# ATM90E26_Featherwing.net
KiCad netlist of a schematic drawn in EAGLE
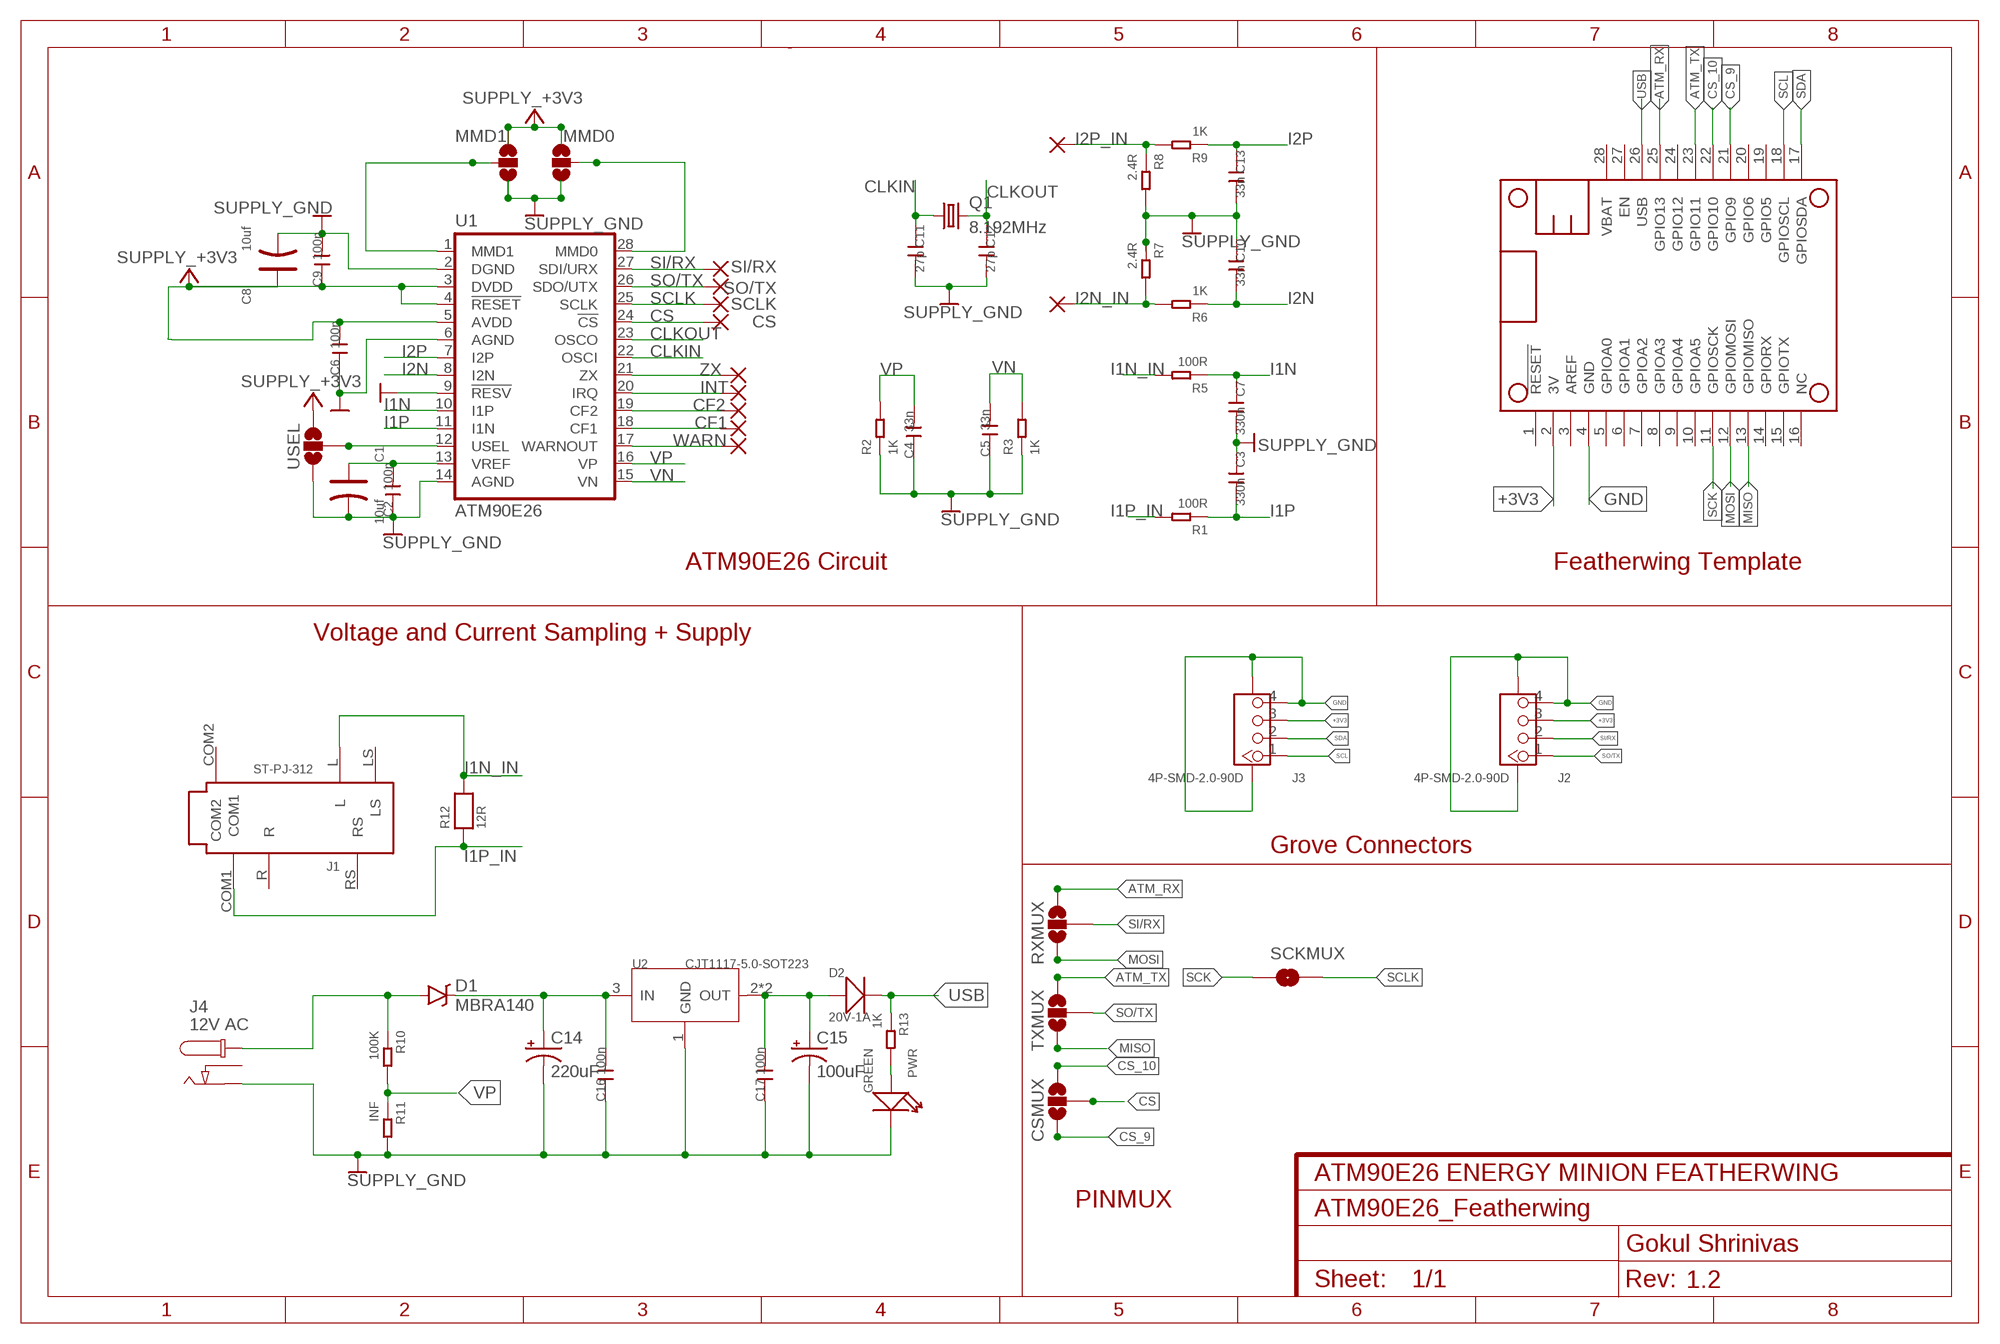
[diagram p0: schematic, sheet 1]

(export (version "E")
  (design (tool "Eeschema 10.0.6"))
  (components
    (comp (ref "C1")
      (value "10uf")
      (footprint "eagle-import:AVX-A")
      (fields (field (name "MPN") "TAJA226*010#NJ"))
      (libsource (lib "eagle-import") (part "TANTALUM-SMD-22UF-10V(AVX-A)"))
    )
    (comp (ref "C2")
      (value "100n")
      (footprint "eagle-import:C0603")
      (libsource (lib "eagle-import") (part "C-0603"))
    )
    (comp (ref "C3")
      (value "330n")
      (footprint "eagle-import:C0603")
      (libsource (lib "eagle-import") (part "C-0603"))
    )
    (comp (ref "C4")
      (value "33n")
      (footprint "eagle-import:C0603")
      (libsource (lib "eagle-import") (part "C-0603"))
    )
    (comp (ref "C5")
      (value "33n")
      (footprint "eagle-import:C0603")
      (libsource (lib "eagle-import") (part "C-0603"))
    )
    (comp (ref "C6")
      (value "100n")
      (footprint "eagle-import:C0603")
      (libsource (lib "eagle-import") (part "C-0603"))
    )
    (comp (ref "C7")
      (value "330n")
      (footprint "eagle-import:C0603")
      (libsource (lib "eagle-import") (part "C-0603"))
    )
    (comp (ref "C8")
      (value "10uf")
      (footprint "eagle-import:AVX-A")
      (fields (field (name "MPN") "TAJA226*010#NJ"))
      (libsource (lib "eagle-import") (part "TANTALUM-SMD-22UF-10V(AVX-A)"))
    )
    (comp (ref "C9")
      (value "100n")
      (footprint "eagle-import:C0603")
      (libsource (lib "eagle-import") (part "C-0603"))
    )
    (comp (ref "C10")
      (value "33n")
      (footprint "eagle-import:C0603")
      (libsource (lib "eagle-import") (part "C-0603"))
    )
    (comp (ref "C11")
      (value "27p")
      (footprint "eagle-import:C0603")
      (libsource (lib "eagle-import") (part "C-0603"))
    )
    (comp (ref "C12")
      (value "27p")
      (footprint "eagle-import:C0603")
      (libsource (lib "eagle-import") (part "C-0603"))
    )
    (comp (ref "C13")
      (value "33n")
      (footprint "eagle-import:C0603")
      (libsource (lib "eagle-import") (part "C-0603"))
    )
    (comp (ref "C14")
      (value "220uF")
      (footprint "eagle-import:140CLH-1010")
      (libsource (lib "eagle-import") (part "CPOL-US140CLH-1010"))
    )
    (comp (ref "C15")
      (value "100uF")
      (footprint "eagle-import:153CLV-0605")
      (libsource (lib "eagle-import") (part "CPOL-US153CLV-0605"))
    )
    (comp (ref "C16")
      (value "100n")
      (footprint "eagle-import:C0603")
      (libsource (lib "eagle-import") (part "C-0603"))
    )
    (comp (ref "C17")
      (value "100n")
      (footprint "eagle-import:C0603")
      (libsource (lib "eagle-import") (part "C-0603"))
    )
    (comp (ref "CF1")
      (value "WIREPADSMD1,27-254")
      (footprint "eagle-import:SMD1,27-2,54")
      (libsource (lib "eagle-import") (part "WIREPADSMD1,27-254"))
    )
    (comp (ref "CF2")
      (value "WIREPADSMD1,27-254")
      (footprint "eagle-import:SMD1,27-2,54")
      (libsource (lib "eagle-import") (part "WIREPADSMD1,27-254"))
    )
    (comp (ref "CS")
      (value "WIREPADSMD1,27-254")
      (footprint "eagle-import:SMD1,27-2,54")
      (libsource (lib "eagle-import") (part "WIREPADSMD1,27-254"))
    )
    (comp (ref "CSMUX")
      (value "JUMPER-PAD-3-NOYES_SILK")
      (footprint "eagle-import:PAD-JUMPER-3-NO_YES_SILK")
      (libsource (lib "eagle-import") (part "JUMPER-PAD-3-NOYES_SILK"))
    )
    (comp (ref "D1")
      (value "MBRA140")
      (footprint "eagle-import:SMA-DIODE")
      (libsource (lib "eagle-import") (part "MBRA140"))
    )
    (comp (ref "D2")
      (value "20V-1A")
      (footprint "eagle-import:SOD-123")
      (fields (field (name "MPN") "B5819W"))
      (libsource (lib "eagle-import") (part "SMD-DIODE-SCHOTTKY-20V-1A(SOD-123)"))
    )
    (comp (ref "I2N_IN")
      (value "WIREPADSMD1,27-254")
      (footprint "eagle-import:SMD1,27-2,54")
      (libsource (lib "eagle-import") (part "WIREPADSMD1,27-254"))
    )
    (comp (ref "I2P_IN")
      (value "WIREPADSMD1,27-254")
      (footprint "eagle-import:SMD1,27-2,54")
      (libsource (lib "eagle-import") (part "WIREPADSMD1,27-254"))
    )
    (comp (ref "INT")
      (value "WIREPADSMD1,27-254")
      (footprint "eagle-import:SMD1,27-2,54")
      (libsource (lib "eagle-import") (part "WIREPADSMD1,27-254"))
    )
    (comp (ref "J1")
      (value "ST-PJ-312")
      (footprint "eagle-import:AUDIO6P-SMD-3.5-14.0X6.4X5.0MM")
      (libsource (lib "eagle-import") (part "AUDIO-JACK-6P-SMD(ST-PJ-312)"))
    )
    (comp (ref "J2")
      (value "4P-SMD-2.0-90D")
      (footprint "eagle-import:HW4-SMD-2.0-90D")
      (libsource (lib "eagle-import") (part "GROVE-CONNECTOR-SMD-90D(4+2P-2.0)"))
    )
    (comp (ref "J3")
      (value "4P-SMD-2.0-90D")
      (footprint "eagle-import:HW4-SMD-2.0-90D")
      (libsource (lib "eagle-import") (part "GROVE-CONNECTOR-SMD-90D(4+2P-2.0)"))
    )
    (comp (ref "J4")
      (value "12V AC")
      (footprint "eagle-import:DC_BARREL_JACK_SMD_2MM")
      (libsource (lib "eagle-import") (part "CON_DC_M-DC_SMD"))
    )
    (comp (ref "MMD0")
      (value "JUMPER-PAD-3-NOFULL_BOX_SILK")
      (footprint "eagle-import:PAD-JUMPER-3-NO_YES_SILK_FULL_BOX")
      (libsource (lib "eagle-import") (part "JUMPER-PAD-3-NOFULL_BOX_SILK"))
    )
    (comp (ref "MMD1")
      (value "JUMPER-PAD-3-NOFULL_BOX_SILK")
      (footprint "eagle-import:PAD-JUMPER-3-NO_YES_SILK_FULL_BOX")
      (libsource (lib "eagle-import") (part "JUMPER-PAD-3-NOFULL_BOX_SILK"))
    )
    (comp (ref "MS1")
      (value "FEATHERWING_NODIM")
      (footprint "eagle-import:FEATHERWING_DIM")
      (libsource (lib "eagle-import") (part "FEATHERWING_NODIM"))
    )
    (comp (ref "PWR")
      (value "GREEN")
      (footprint "eagle-import:LED-0603")
      (libsource (lib "eagle-import") (part "LED'0603'"))
    )
    (comp (ref "Q1")
      (value "8.192MHz")
      (footprint "eagle-import:HC49UP")
      (libsource (lib "eagle-import") (part "CRYSTALHC49UP"))
    )
    (comp (ref "R1")
      (value "100R")
      (footprint "eagle-import:R0603")
      (fields (field (name "MPN") "RC0603FR-071KL"))
      (libsource (lib "eagle-import") (part "SMD-RES-1K(0603)"))
    )
    (comp (ref "R2")
      (value "1K")
      (footprint "eagle-import:R0603")
      (fields (field (name "MPN") "RC0603FR-071KL"))
      (libsource (lib "eagle-import") (part "SMD-RES-1K(0603)"))
    )
    (comp (ref "R3")
      (value "1K")
      (footprint "eagle-import:R0603")
      (fields (field (name "MPN") "RC0603FR-071KL"))
      (libsource (lib "eagle-import") (part "SMD-RES-1K(0603)"))
    )
    (comp (ref "R5")
      (value "100R")
      (footprint "eagle-import:R0603")
      (fields (field (name "MPN") "RC0603FR-071KL"))
      (libsource (lib "eagle-import") (part "SMD-RES-1K(0603)"))
    )
    (comp (ref "R6")
      (value "1K")
      (footprint "eagle-import:R0603")
      (fields (field (name "MPN") "RC0603FR-071KL"))
      (libsource (lib "eagle-import") (part "SMD-RES-1K(0603)"))
    )
    (comp (ref "R7")
      (value "2.4R")
      (footprint "eagle-import:R0603")
      (fields (field (name "MPN") "RC0603FR-071KL"))
      (libsource (lib "eagle-import") (part "SMD-RES-1K(0603)"))
    )
    (comp (ref "R8")
      (value "2.4R")
      (footprint "eagle-import:R0603")
      (fields (field (name "MPN") "RC0603FR-071KL"))
      (libsource (lib "eagle-import") (part "SMD-RES-1K(0603)"))
    )
    (comp (ref "R9")
      (value "1K")
      (footprint "eagle-import:R0603")
      (fields (field (name "MPN") "RC0603FR-071KL"))
      (libsource (lib "eagle-import") (part "SMD-RES-1K(0603)"))
    )
    (comp (ref "R10")
      (value "100K")
      (footprint "eagle-import:R0603")
      (fields (field (name "MPN") "RC0603JR-070RL"))
      (libsource (lib "eagle-import") (part "SMD-RES-0R(0603)"))
    )
    (comp (ref "R11")
      (value "INF")
      (footprint "eagle-import:R0603")
      (fields (field (name "MPN") "RC0603JR-070RL"))
      (libsource (lib "eagle-import") (part "SMD-RES-0R(0603)"))
    )
    (comp (ref "R12")
      (value "12R")
      (footprint "eagle-import:0805")
      (libsource (lib "eagle-import") (part "RESISTOR0805"))
    )
    (comp (ref "R13")
      (value "1K")
      (footprint "eagle-import:R0603")
      (fields (field (name "MPN") "RC0603JR-070RL"))
      (libsource (lib "eagle-import") (part "SMD-RES-0R(0603)"))
    )
    (comp (ref "RXMUX")
      (value "JUMPER-PAD-3-NOYES_SILK")
      (footprint "eagle-import:PAD-JUMPER-3-NO_YES_SILK")
      (libsource (lib "eagle-import") (part "JUMPER-PAD-3-NOYES_SILK"))
    )
    (comp (ref "SCKMUX")
      (value "JUMPER-PAD-2-NOYES_SILK")
      (footprint "eagle-import:PAD-JUMPER-2-NO_YES_SILK")
      (libsource (lib "eagle-import") (part "JUMPER-PAD-2-NOYES_SILK"))
    )
    (comp (ref "SCLK")
      (value "WIREPADSMD1,27-254")
      (footprint "eagle-import:SMD1,27-2,54")
      (libsource (lib "eagle-import") (part "WIREPADSMD1,27-254"))
    )
    (comp (ref "SI/RX")
      (value "WIREPADSMD1,27-254")
      (footprint "eagle-import:SMD1,27-2,54")
      (libsource (lib "eagle-import") (part "WIREPADSMD1,27-254"))
    )
    (comp (ref "SO/TX")
      (value "WIREPADSMD1,27-254")
      (footprint "eagle-import:SMD1,27-2,54")
      (libsource (lib "eagle-import") (part "WIREPADSMD1,27-254"))
    )
    (comp (ref "TXMUX")
      (value "JUMPER-PAD-3-NOYES_SILK")
      (footprint "eagle-import:PAD-JUMPER-3-NO_YES_SILK")
      (libsource (lib "eagle-import") (part "JUMPER-PAD-3-NOYES_SILK"))
    )
    (comp (ref "U1")
      (value "ATM90E26")
      (footprint "eagle-import:SSOP-28")
      (fields (field (name "MANF") "Atmel"))
      (libsource (lib "eagle-import") (part "ATM90E26"))
    )
    (comp (ref "U2")
      (value "CJT1117-5.0-SOT223")
      (footprint "eagle-import:SOT-223")
      (fields (field (name "MPN") "CJT1117-5.0"))
      (libsource (lib "eagle-import") (part "PMIC-CJT1117-5.0(SOT223)"))
    )
    (comp (ref "USEL")
      (value "JUMPER-PAD-3-NOFULL_BOX_SILK")
      (footprint "eagle-import:PAD-JUMPER-3-NO_YES_SILK_FULL_BOX")
      (libsource (lib "eagle-import") (part "JUMPER-PAD-3-NOFULL_BOX_SILK"))
    )
    (comp (ref "WARN")
      (value "WIREPADSMD1,27-254")
      (footprint "eagle-import:SMD1,27-2,54")
      (libsource (lib "eagle-import") (part "WIREPADSMD1,27-254"))
    )
    (comp (ref "ZX")
      (value "WIREPADSMD1,27-254")
      (footprint "eagle-import:SMD1,27-2,54")
      (libsource (lib "eagle-import") (part "WIREPADSMD1,27-254"))
    )
  )
  (nets
    (net (code "1") (name "+3V3") (class "Default")
      (node (ref "C6") (pin "2") (pinfunction "2_2") (pintype "passive"))
      (node (ref "C8") (pin "+") (pinfunction "+_+") (pintype "passive"))
      (node (ref "C9") (pin "1") (pinfunction "1_1") (pintype "passive"))
      (node (ref "J2") (pin "3") (pinfunction "3_3") (pintype "bidirectional"))
      (node (ref "J3") (pin "3") (pinfunction "3_3") (pintype "bidirectional"))
      (node (ref "MMD0") (pin "3") (pinfunction "3_3") (pintype "passive"))
      (node (ref "MMD1") (pin "1") (pinfunction "1_1") (pintype "passive"))
      (node (ref "MS1") (pin "2") (pinfunction "3V_2") (pintype "power_in"))
      (node (ref "U1") (pin "3") (pinfunction "DVDD_3") (pintype "power_in"))
      (node (ref "U1") (pin "4") (pinfunction "~{RESET}_4") (pintype "input"))
      (node (ref "U1") (pin "5") (pinfunction "AVDD_5") (pintype "power_in"))
      (node (ref "USEL") (pin "3") (pinfunction "3_3") (pintype "passive"))
    )
    (net (code "2") (name "/CLKIN") (class "Default")
      (node (ref "C11") (pin "1") (pinfunction "1_1") (pintype "passive"))
      (node (ref "Q1") (pin "1") (pinfunction "1_1") (pintype "passive"))
      (node (ref "U1") (pin "22") (pinfunction "OSCI_22") (pintype "input"))
    )
    (net (code "3") (name "/CLKOUT") (class "Default")
      (node (ref "C12") (pin "1") (pinfunction "1_1") (pintype "passive"))
      (node (ref "Q1") (pin "2") (pinfunction "2_2") (pintype "passive"))
      (node (ref "U1") (pin "23") (pinfunction "OSCO_23") (pintype "output"))
    )
    (net (code "4") (name "/I1N") (class "Default")
      (node (ref "C7") (pin "1") (pinfunction "1_1") (pintype "passive"))
      (node (ref "R5") (pin "1") (pinfunction "1_1") (pintype "passive"))
      (node (ref "U1") (pin "10") (pinfunction "I1P_10") (pintype "input"))
    )
    (net (code "5") (name "/I1N_IN") (class "Default")
      (node (ref "J1") (pin "L") (pinfunction "L_L") (pintype "bidirectional"))
      (node (ref "R12") (pin "2") (pinfunction "2_2") (pintype "passive"))
      (node (ref "R5") (pin "2") (pinfunction "2_2") (pintype "passive"))
    )
    (net (code "6") (name "/I1P") (class "Default")
      (node (ref "C3") (pin "2") (pinfunction "2_2") (pintype "passive"))
      (node (ref "R1") (pin "1") (pinfunction "1_1") (pintype "passive"))
      (node (ref "U1") (pin "11") (pinfunction "I1N_11") (pintype "input"))
    )
    (net (code "7") (name "/I1P_IN") (class "Default")
      (node (ref "J1") (pin "COM1") (pinfunction "COM1_COM1") (pintype "bidirectional"))
      (node (ref "R1") (pin "2") (pinfunction "2_2") (pintype "passive"))
      (node (ref "R12") (pin "1") (pinfunction "1_1") (pintype "passive"))
    )
    (net (code "8") (name "/I2N") (class "Default")
      (node (ref "C10") (pin "2") (pinfunction "2_2") (pintype "passive"))
      (node (ref "R6") (pin "1") (pinfunction "1_1") (pintype "passive"))
      (node (ref "U1") (pin "8") (pinfunction "I2N_8") (pintype "input"))
    )
    (net (code "9") (name "/I2N_IN") (class "Default")
      (node (ref "I2N_IN") (pin "1") (pinfunction "P_1") (pintype "passive"))
      (node (ref "R6") (pin "2") (pinfunction "2_2") (pintype "passive"))
      (node (ref "R7") (pin "2") (pinfunction "2_2") (pintype "passive"))
    )
    (net (code "10") (name "/I2P") (class "Default")
      (node (ref "C13") (pin "1") (pinfunction "1_1") (pintype "passive"))
      (node (ref "R9") (pin "1") (pinfunction "1_1") (pintype "passive"))
      (node (ref "U1") (pin "7") (pinfunction "I2P_7") (pintype "input"))
    )
    (net (code "11") (name "/I2P_IN") (class "Default")
      (node (ref "I2P_IN") (pin "1") (pinfunction "P_1") (pintype "passive"))
      (node (ref "R8") (pin "1") (pinfunction "1_1") (pintype "passive"))
      (node (ref "R9") (pin "2") (pinfunction "2_2") (pintype "passive"))
    )
    (net (code "12") (name "/VBAT") (class "Default")
      (node (ref "MS1") (pin "28") (pinfunction "VBAT_28") (pintype "power_in"))
    )
    (net (code "13") (name "/VN") (class "Default")
      (node (ref "C5") (pin "2") (pinfunction "2_2") (pintype "passive"))
      (node (ref "R3") (pin "2") (pinfunction "2_2") (pintype "passive"))
      (node (ref "U1") (pin "15") (pinfunction "VN_15") (pintype "input"))
    )
    (net (code "14") (name "ATM_RX") (class "Default")
      (node (ref "MS1") (pin "25") (pinfunction "GPIO13_25") (pintype "bidirectional"))
      (node (ref "RXMUX") (pin "3") (pinfunction "3_3") (pintype "passive"))
    )
    (net (code "15") (name "ATM_TX") (class "Default")
      (node (ref "MS1") (pin "23") (pinfunction "GPIO11_23") (pintype "bidirectional"))
      (node (ref "TXMUX") (pin "3") (pinfunction "3_3") (pintype "passive"))
    )
    (net (code "16") (name "CS") (class "Default")
      (node (ref "CS") (pin "1") (pinfunction "P_1") (pintype "passive"))
      (node (ref "CSMUX") (pin "2") (pinfunction "2_2") (pintype "passive"))
      (node (ref "U1") (pin "24") (pinfunction "~{CS}_24") (pintype "input"))
    )
    (net (code "17") (name "CS_9") (class "Default")
      (node (ref "CSMUX") (pin "1") (pinfunction "1_1") (pintype "passive"))
      (node (ref "MS1") (pin "21") (pinfunction "GPIO9_21") (pintype "bidirectional"))
    )
    (net (code "18") (name "CS_10") (class "Default")
      (node (ref "CSMUX") (pin "3") (pinfunction "3_3") (pintype "passive"))
      (node (ref "MS1") (pin "22") (pinfunction "GPIO10_22") (pintype "bidirectional"))
    )
    (net (code "19") (name "GND") (class "Default")
      (node (ref "C1") (pin "-") (pinfunction "-_-") (pintype "passive"))
      (node (ref "C10") (pin "1") (pinfunction "1_1") (pintype "passive"))
      (node (ref "C11") (pin "2") (pinfunction "2_2") (pintype "passive"))
      (node (ref "C12") (pin "2") (pinfunction "2_2") (pintype "passive"))
      (node (ref "C13") (pin "2") (pinfunction "2_2") (pintype "passive"))
      (node (ref "C14") (pin "-") (pinfunction "-_-") (pintype "passive"))
      (node (ref "C15") (pin "-") (pinfunction "-_-") (pintype "passive"))
      (node (ref "C16") (pin "1") (pinfunction "1_1") (pintype "passive"))
      (node (ref "C17") (pin "1") (pinfunction "1_1") (pintype "passive"))
      (node (ref "C2") (pin "1") (pinfunction "1_1") (pintype "passive"))
      (node (ref "C3") (pin "1") (pinfunction "1_1") (pintype "passive"))
      (node (ref "C4") (pin "1") (pinfunction "1_1") (pintype "passive"))
      (node (ref "C5") (pin "1") (pinfunction "1_1") (pintype "passive"))
      (node (ref "C6") (pin "1") (pinfunction "1_1") (pintype "passive"))
      (node (ref "C7") (pin "2") (pinfunction "2_2") (pintype "passive"))
      (node (ref "C8") (pin "-") (pinfunction "-_-") (pintype "passive"))
      (node (ref "C9") (pin "2") (pinfunction "2_2") (pintype "passive"))
      (node (ref "J2") (pin "4") (pinfunction "4_4") (pintype "bidirectional"))
      (node (ref "J2") (pin "SS1") (pinfunction "SS1_SS1") (pintype "bidirectional"))
      (node (ref "J2") (pin "SS2") (pinfunction "SS2_SS2") (pintype "bidirectional"))
      (node (ref "J3") (pin "4") (pinfunction "4_4") (pintype "bidirectional"))
      (node (ref "J3") (pin "SS1") (pinfunction "SS1_SS1") (pintype "bidirectional"))
      (node (ref "J3") (pin "SS2") (pinfunction "SS2_SS2") (pintype "bidirectional"))
      (node (ref "J4") (pin "P2") (pinfunction "P2_P2") (pintype "passive"))
      (node (ref "MMD0") (pin "1") (pinfunction "1_1") (pintype "passive"))
      (node (ref "MMD1") (pin "3") (pinfunction "3_3") (pintype "passive"))
      (node (ref "MS1") (pin "4") (pinfunction "GND_4") (pintype "power_in"))
      (node (ref "PWR") (pin "-") (pinfunction "-_-") (pintype "passive"))
      (node (ref "R11") (pin "2") (pinfunction "2_2") (pintype "passive"))
      (node (ref "R2") (pin "1") (pinfunction "1_1") (pintype "passive"))
      (node (ref "R3") (pin "1") (pinfunction "1_1") (pintype "passive"))
      (node (ref "R7") (pin "1") (pinfunction "1_1") (pintype "passive"))
      (node (ref "R8") (pin "2") (pinfunction "2_2") (pintype "passive"))
      (node (ref "U1") (pin "14") (pinfunction "AGND_14") (pintype "power_in"))
      (node (ref "U1") (pin "2") (pinfunction "DGND_2") (pintype "power_in"))
      (node (ref "U1") (pin "6") (pinfunction "AGND_6") (pintype "power_in"))
      (node (ref "U1") (pin "9") (pinfunction "~{RESV}_9") (pintype "input"))
      (node (ref "U2") (pin "1") (pinfunction "GND_1") (pintype "bidirectional"))
      (node (ref "USEL") (pin "1") (pinfunction "1_1") (pintype "passive"))
    )
    (net (code "20") (name "MISO") (class "Default")
      (node (ref "MS1") (pin "13") (pinfunction "GPIOMISO_13") (pintype "bidirectional"))
      (node (ref "TXMUX") (pin "1") (pinfunction "1_1") (pintype "passive"))
    )
    (net (code "21") (name "MOSI") (class "Default")
      (node (ref "MS1") (pin "12") (pinfunction "GPIOMOSI_12") (pintype "bidirectional"))
      (node (ref "RXMUX") (pin "1") (pinfunction "1_1") (pintype "passive"))
    )
    (net (code "22") (name "Net-(C15-Pad+)") (class "Default")
      (node (ref "C15") (pin "+") (pinfunction "+_+") (pintype "passive"))
      (node (ref "C17") (pin "2") (pinfunction "2_2") (pintype "passive"))
      (node (ref "D2") (pin "+") (pinfunction "+_+") (pintype "passive"))
      (node (ref "U2") (pin "2") (pinfunction "OUT_2") (pintype "bidirectional"))
      (node (ref "U2") (pin "TER") (pinfunction "OUT_TER") (pintype "bidirectional"))
    )
    (net (code "23") (name "Net-(CF1-P)") (class "Default")
      (node (ref "CF1") (pin "1") (pinfunction "P_1") (pintype "passive"))
      (node (ref "U1") (pin "18") (pinfunction "CF1_18") (pintype "output"))
    )
    (net (code "24") (name "Net-(CF2-P)") (class "Default")
      (node (ref "CF2") (pin "1") (pinfunction "P_1") (pintype "passive"))
      (node (ref "U1") (pin "19") (pinfunction "CF2_19") (pintype "output"))
    )
    (net (code "25") (name "Net-(INT-P)") (class "Default")
      (node (ref "INT") (pin "1") (pinfunction "P_1") (pintype "passive"))
      (node (ref "U1") (pin "20") (pinfunction "IRQ_20") (pintype "output"))
    )
    (net (code "26") (name "Net-(J4-P1)") (class "Default")
      (node (ref "D1") (pin "A") (pinfunction "A_A") (pintype "passive"))
      (node (ref "J4") (pin "P1@2") (pinfunction "P1_P1@2") (pintype "passive"))
      (node (ref "R10") (pin "1") (pinfunction "1_1") (pintype "passive"))
    )
    (net (code "27") (name "Net-(PWR-Pad+)") (class "Default")
      (node (ref "PWR") (pin "+") (pinfunction "+_+") (pintype "passive"))
      (node (ref "R13") (pin "2") (pinfunction "2_2") (pintype "passive"))
    )
    (net (code "28") (name "Net-(U1-MMD0)") (class "Default")
      (node (ref "MMD0") (pin "2") (pinfunction "2_2") (pintype "passive"))
      (node (ref "U1") (pin "28") (pinfunction "MMD0_28") (pintype "input"))
    )
    (net (code "29") (name "Net-(U1-MMD1)") (class "Default")
      (node (ref "MMD1") (pin "2") (pinfunction "2_2") (pintype "passive"))
      (node (ref "U1") (pin "1") (pinfunction "MMD1_1") (pintype "input"))
    )
    (net (code "30") (name "Net-(U1-USEL)") (class "Default")
      (node (ref "U1") (pin "12") (pinfunction "USEL_12") (pintype "input"))
      (node (ref "USEL") (pin "2") (pinfunction "2_2") (pintype "passive"))
    )
    (net (code "31") (name "Net-(U1-VREF)") (class "Default")
      (node (ref "C1") (pin "+") (pinfunction "+_+") (pintype "passive"))
      (node (ref "C2") (pin "2") (pinfunction "2_2") (pintype "passive"))
      (node (ref "U1") (pin "13") (pinfunction "VREF_13") (pintype "power_in"))
    )
    (net (code "32") (name "Net-(U1-WARNOUT)") (class "Default")
      (node (ref "U1") (pin "17") (pinfunction "WARNOUT_17") (pintype "output"))
      (node (ref "WARN") (pin "1") (pinfunction "P_1") (pintype "passive"))
    )
    (net (code "33") (name "Net-(U1-ZX)") (class "Default")
      (node (ref "U1") (pin "21") (pinfunction "ZX_21") (pintype "bidirectional"))
      (node (ref "ZX") (pin "1") (pinfunction "P_1") (pintype "passive"))
    )
    (net (code "34") (name "Net-(U2-IN)") (class "Default")
      (node (ref "C14") (pin "+") (pinfunction "+_+") (pintype "passive"))
      (node (ref "C16") (pin "2") (pinfunction "2_2") (pintype "passive"))
      (node (ref "D1") (pin "C") (pinfunction "C_C") (pintype "passive"))
      (node (ref "U2") (pin "3") (pinfunction "IN_3") (pintype "bidirectional"))
    )
    (net (code "35") (name "SCK") (class "Default")
      (node (ref "MS1") (pin "11") (pinfunction "GPIOSCK_11") (pintype "bidirectional"))
      (node (ref "SCKMUX") (pin "1") (pinfunction "1_1") (pintype "passive"))
    )
    (net (code "36") (name "SCL") (class "Default")
      (node (ref "J3") (pin "1") (pinfunction "1_1") (pintype "bidirectional"))
      (node (ref "MS1") (pin "18") (pinfunction "GPIOSCL_18") (pintype "bidirectional"))
    )
    (net (code "37") (name "SCLK") (class "Default")
      (node (ref "SCKMUX") (pin "2") (pinfunction "2_2") (pintype "passive"))
      (node (ref "SCLK") (pin "1") (pinfunction "P_1") (pintype "passive"))
      (node (ref "U1") (pin "25") (pinfunction "SCLK_25") (pintype "input"))
    )
    (net (code "38") (name "SDA") (class "Default")
      (node (ref "J3") (pin "2") (pinfunction "2_2") (pintype "bidirectional"))
      (node (ref "MS1") (pin "17") (pinfunction "GPIOSDA_17") (pintype "bidirectional"))
    )
    (net (code "39") (name "SI{slash}RX") (class "Default")
      (node (ref "J2") (pin "2") (pinfunction "2_2") (pintype "bidirectional"))
      (node (ref "RXMUX") (pin "2") (pinfunction "2_2") (pintype "passive"))
      (node (ref "SI/RX") (pin "1") (pinfunction "P_1") (pintype "passive"))
      (node (ref "U1") (pin "27") (pinfunction "SDI/URX_27") (pintype "input"))
    )
    (net (code "40") (name "SO{slash}TX") (class "Default")
      (node (ref "J2") (pin "1") (pinfunction "1_1") (pintype "bidirectional"))
      (node (ref "SO/TX") (pin "1") (pinfunction "P_1") (pintype "passive"))
      (node (ref "TXMUX") (pin "2") (pinfunction "2_2") (pintype "passive"))
      (node (ref "U1") (pin "26") (pinfunction "SDO/UTX_26") (pintype "output"))
    )
    (net (code "41") (name "USB") (class "Default")
      (node (ref "D2") (pin "-") (pinfunction "-_-") (pintype "passive"))
      (node (ref "MS1") (pin "26") (pinfunction "USB_26") (pintype "power_in"))
      (node (ref "R13") (pin "1") (pinfunction "1_1") (pintype "passive"))
    )
    (net (code "42") (name "VP") (class "Default")
      (node (ref "C4") (pin "2") (pinfunction "2_2") (pintype "passive"))
      (node (ref "R10") (pin "2") (pinfunction "2_2") (pintype "passive"))
      (node (ref "R11") (pin "1") (pinfunction "1_1") (pintype "passive"))
      (node (ref "R2") (pin "2") (pinfunction "2_2") (pintype "passive"))
      (node (ref "U1") (pin "16") (pinfunction "VP_16") (pintype "input"))
    )
    (net (code "43") (name "unconnected-(J1-PadCOM2)") (class "Default")
      (node (ref "J1") (pin "COM2") (pinfunction "COM2_COM2") (pintype "bidirectional"))
    )
    (net (code "44") (name "unconnected-(J1-PadLS)") (class "Default")
      (node (ref "J1") (pin "LS") (pinfunction "LS_LS") (pintype "bidirectional"))
    )
    (net (code "45") (name "unconnected-(J1-PadR)") (class "Default")
      (node (ref "J1") (pin "R") (pinfunction "R_R") (pintype "bidirectional"))
    )
    (net (code "46") (name "unconnected-(J1-PadRS)") (class "Default")
      (node (ref "J1") (pin "RS") (pinfunction "RS_RS") (pintype "bidirectional"))
    )
    (net (code "47") (name "unconnected-(J4-PadP3)") (class "Default")
      (node (ref "J4") (pin "P3") (pinfunction "P3_P3") (pintype "passive"))
    )
    (net (code "48") (name "unconnected-(MS1-AREF-Pad3)") (class "Default")
      (node (ref "MS1") (pin "3") (pinfunction "AREF_3") (pintype "passive"))
    )
    (net (code "49") (name "unconnected-(MS1-EN-Pad27)") (class "Default")
      (node (ref "MS1") (pin "27") (pinfunction "EN_27") (pintype "passive"))
    )
    (net (code "50") (name "unconnected-(MS1-GPIO5-Pad19)") (class "Default")
      (node (ref "MS1") (pin "19") (pinfunction "GPIO5_19") (pintype "bidirectional"))
    )
    (net (code "51") (name "unconnected-(MS1-GPIO6-Pad20)") (class "Default")
      (node (ref "MS1") (pin "20") (pinfunction "GPIO6_20") (pintype "bidirectional"))
    )
    (net (code "52") (name "unconnected-(MS1-GPIO12-Pad24)") (class "Default")
      (node (ref "MS1") (pin "24") (pinfunction "GPIO12_24") (pintype "bidirectional"))
    )
    (net (code "53") (name "unconnected-(MS1-GPIOA0-Pad5)") (class "Default")
      (node (ref "MS1") (pin "5") (pinfunction "GPIOA0_5") (pintype "bidirectional"))
    )
    (net (code "54") (name "unconnected-(MS1-GPIOA1-Pad6)") (class "Default")
      (node (ref "MS1") (pin "6") (pinfunction "GPIOA1_6") (pintype "bidirectional"))
    )
    (net (code "55") (name "unconnected-(MS1-GPIOA2-Pad7)") (class "Default")
      (node (ref "MS1") (pin "7") (pinfunction "GPIOA2_7") (pintype "bidirectional"))
    )
    (net (code "56") (name "unconnected-(MS1-GPIOA3-Pad8)") (class "Default")
      (node (ref "MS1") (pin "8") (pinfunction "GPIOA3_8") (pintype "bidirectional"))
    )
    (net (code "57") (name "unconnected-(MS1-GPIOA4-Pad9)") (class "Default")
      (node (ref "MS1") (pin "9") (pinfunction "GPIOA4_9") (pintype "bidirectional"))
    )
    (net (code "58") (name "unconnected-(MS1-GPIOA5-Pad10)") (class "Default")
      (node (ref "MS1") (pin "10") (pinfunction "GPIOA5_10") (pintype "bidirectional"))
    )
    (net (code "59") (name "unconnected-(MS1-GPIORX-Pad14)") (class "Default")
      (node (ref "MS1") (pin "14") (pinfunction "GPIORX_14") (pintype "bidirectional"))
    )
    (net (code "60") (name "unconnected-(MS1-GPIOTX-Pad15)") (class "Default")
      (node (ref "MS1") (pin "15") (pinfunction "GPIOTX_15") (pintype "bidirectional"))
    )
    (net (code "61") (name "unconnected-(MS1-NC-Pad16)") (class "Default")
      (node (ref "MS1") (pin "16") (pinfunction "NC_16") (pintype "passive"))
    )
    (net (code "62") (name "unconnected-(MS1-~{RESET}-Pad1)") (class "Default")
      (node (ref "MS1") (pin "1") (pinfunction "~{RESET}_1") (pintype "input"))
    )
  )
)
